# H03R00-T.net
KiCad netlist of a schematic drawn in EAGLE
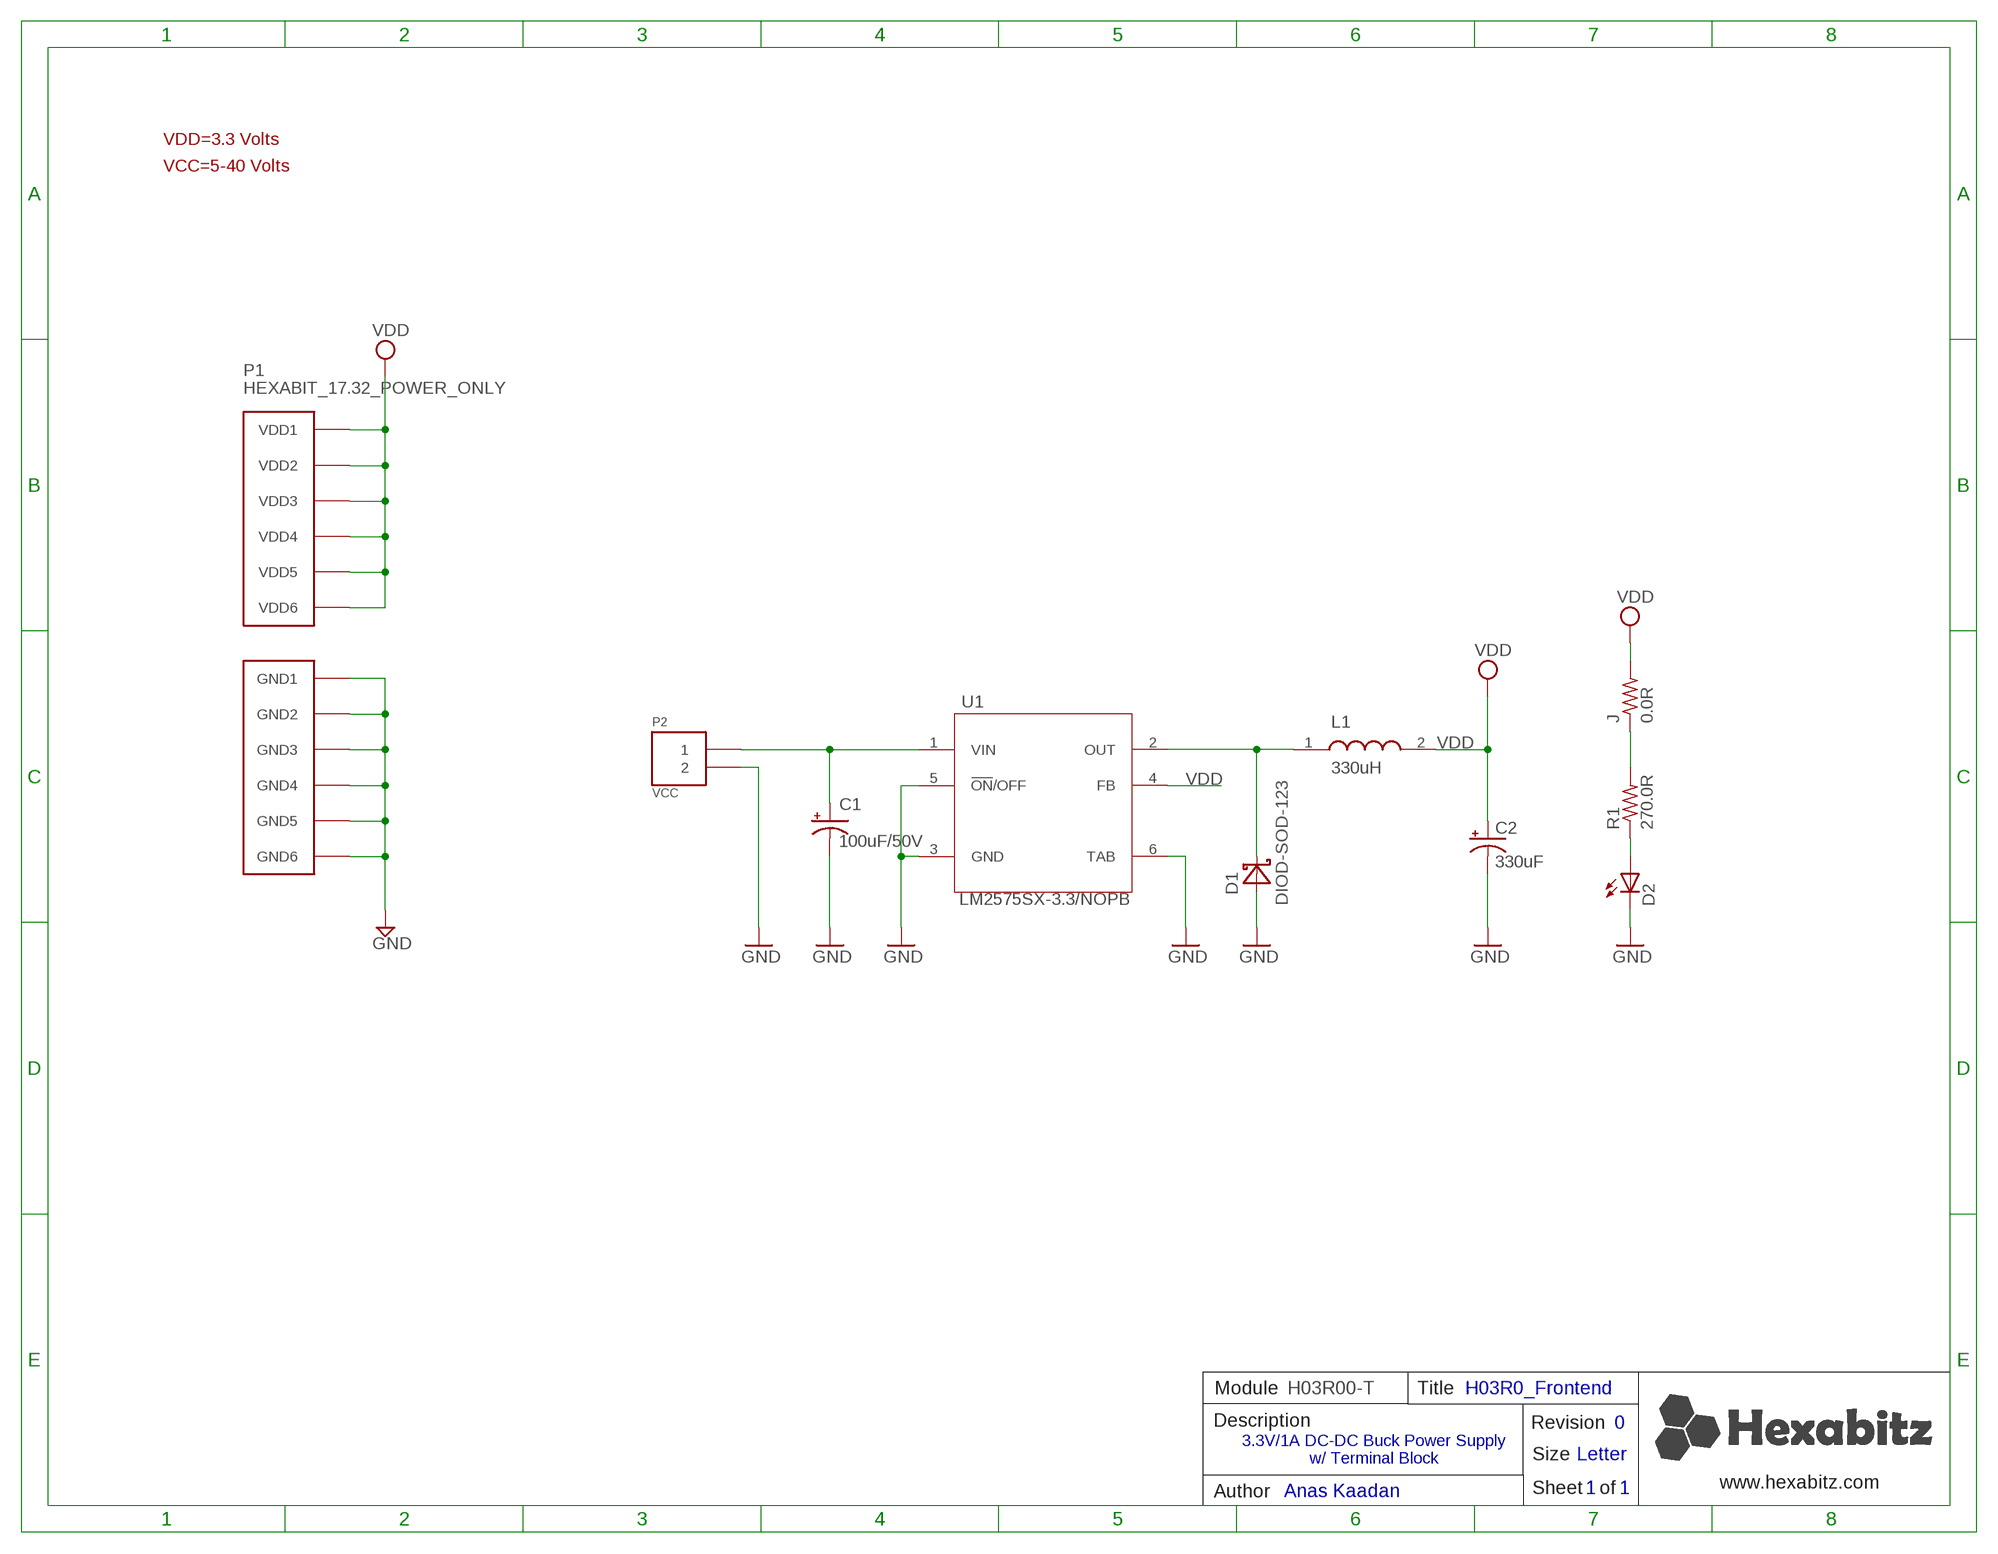
[diagram p0: schematic, sheet 1]

(export (version "E")
  (design (tool "Eeschema 10.0.6"))
  (components
    (comp (ref "C1")
      (value "100uF/50V")
      (footprint "eagle-import:E3,5-8")
      (fields
        (field (name "CAPACITANCE") "100F")
        (field (name "CPACITANCE_RATING") "±20%")
        (field (name "MFN") "Nichicon")
        (field (name "MPN") "UVR1H101MPD1TD")
        (field (name "OCTOPART_ID") "913e58b97f3b4ef9")
        (field (name "OCTOPART_URL") "http://octopart.com/uvr1h101mpd1td-nichicon-9292643")
        (field (name "VOLTAGE_RATING_DC") "50.0 V")
      )
      (libsource (lib "eagle-import") (part "CPOL-US"))
    )
    (comp (ref "C2")
      (value "330uF")
      (footprint "eagle-import:CAPPM7343X200N")
      (fields
        (field (name "MANUFACTURER_PART_NUMBER") "6TPC330MA")
        (field (name "MOUSER_PART_NUMBER") "667-6TPC330MA")
        (field (name "RS_PART_NUMBER") "1666900")
      )
      (libsource (lib "eagle-import") (part "AVX-E"))
    )
    (comp (ref "D1")
      (value "DIOD-SOD-123")
      (footprint "eagle-import:SOD123")
      (fields
        (field (name "CAPACITANCE") "1.1e-10 F")
        (field (name "CURRENT_RATING") "1.0 A")
        (field (name "MFN") "diodes")
        (field (name "MPN") "1N5819HW-7-F")
        (field (name "OCTOPART_ID") "e83e2130232537f9")
        (field (name "OCTOPART_URL") "https://octopart.com/1n5819hw-7-f-diodes+inc.-323197")
        (field (name "VOLTAGE_RATING_DC") "40.0 V")
      )
      (libsource (lib "eagle-import") (part "DIOD-SOD-123"))
    )
    (comp (ref "D2")
      (value "VLMS1300-GS08")
      (footprint "eagle-import:VLMS1300-GS08")
      (fields
        (field (name "MFN") "Vishay")
        (field (name "MPN") "VLMTG1300-GS08")
        (field (name "OCTOPART_URL") "http://octopart.com/vlmtg1300-gs08-vishay-21709202")
      )
      (libsource (lib "eagle-import") (part "VLMS1300-GS08"))
    )
    (comp (ref "J")
      (value "0.0R")
      (footprint "eagle-import:R-0603")
      (fields
        (field (name "MFN") "Yageo")
        (field (name "MPN") "RC0603JR-070RL")
        (field (name "OCTOPART_URL") "https://octopart.com/crcw06030000z0eahp-vishay-44320230")
        (field (name "RESISTANCE") "0.0 Ω")
      )
      (libsource (lib "eagle-import") (part "R-0603"))
    )
    (comp (ref "L1")
      (value "330uH")
      (footprint "eagle-import:SRR1280-150M")
      (fields
        (field (name "MANUFACTURER_PART_NUMBER") "SRR1280-331K")
        (field (name "MOUSER_PART_NUMBER") "652-SRR1280-331K")
        (field (name "RS_PART_NUMBER") "1728540")
      )
      (libsource (lib "eagle-import") (part "SRR1280-331K"))
    )
    (comp (ref "P1")
      (value "HEXABIT_17.32_POWER_ONLY")
      (footprint "eagle-import:HEXABIT_17.32_POWER_ONLY")
      (libsource (lib "eagle-import") (part "HEXABIT_?_POWER_ONLY17.32"))
    )
    (comp (ref "P2")
      (value "VCC")
      (footprint "eagle-import:1546111-2")
      (fields (field (name "MPN") "1546111-2"))
      (libsource (lib "eagle-import") (part "1546111-2"))
    )
    (comp (ref "R1")
      (value "270.0R")
      (footprint "eagle-import:R-0603")
      (fields
        (field (name "MFN") "Yageo")
        (field (name "MPN") "RC0603FR-07270RL")
        (field (name "OCTOPART_URL") "https://octopart.com/crcw0603270rjnea-vishay-39784736")
        (field (name "RESISTANCE") "270.0 Ω")
        (field (name "TOLERANCE") "±5%")
      )
      (libsource (lib "eagle-import") (part "R-0603"))
    )
    (comp (ref "U1")
      (value "LM2575SX-3.3/NOPB")
      (footprint "eagle-import:TO170P1435X457-6N")
      (fields
        (field (name "DIGI-KEY_PART_NUMBER") "LM2575SX-3.3/NOPBCT-ND")
        (field (name "MF") "Texas Instruments")
      )
      (libsource (lib "eagle-import") (part "LM2575SX-3.3/NOPB"))
    )
  )
  (nets
    (net (code "1") (name "GND") (class "Default")
      (node (ref "C1") (pin "-") (pinfunction "-_-") (pintype "passive"))
      (node (ref "C2") (pin "2") (pinfunction "-_2") (pintype "passive"))
      (node (ref "D1") (pin "1") (pinfunction "A_1") (pintype "passive"))
      (node (ref "D2") (pin "C") (pinfunction "C_C") (pintype "passive"))
      (node (ref "P1") (pin "PAD_PD10") (pinfunction "GND4_PAD_PD10") (pintype "power_in"))
      (node (ref "P1") (pin "PAD_PD11") (pinfunction "GND5_PAD_PD11") (pintype "power_in"))
      (node (ref "P1") (pin "PAD_PD12") (pinfunction "GND6_PAD_PD12") (pintype "power_in"))
      (node (ref "P1") (pin "PAD_PD7") (pinfunction "GND1_PAD_PD7") (pintype "power_in"))
      (node (ref "P1") (pin "PAD_PD8") (pinfunction "GND2_PAD_PD8") (pintype "power_in"))
      (node (ref "P1") (pin "PAD_PD9") (pinfunction "GND3_PAD_PD9") (pintype "power_in"))
      (node (ref "P2") (pin "2") (pinfunction "2_2") (pintype "power_in"))
      (node (ref "U1") (pin "3") (pinfunction "GND_3") (pintype "passive"))
      (node (ref "U1") (pin "5") (pinfunction "ON/OFF_5") (pintype "input"))
      (node (ref "U1") (pin "6") (pinfunction "TAB_6") (pintype "passive"))
    )
    (net (code "2") (name "Net-(D1-C)") (class "Default")
      (node (ref "D1") (pin "2") (pinfunction "C_2") (pintype "passive"))
      (node (ref "L1") (pin "1") (pinfunction "1_1") (pintype "bidirectional"))
      (node (ref "U1") (pin "2") (pinfunction "OUT_2") (pintype "output"))
    )
    (net (code "3") (name "Net-(D2-PadA)") (class "Default")
      (node (ref "D2") (pin "A") (pinfunction "A_A") (pintype "passive"))
      (node (ref "R1") (pin "1") (pinfunction "1_1") (pintype "passive"))
    )
    (net (code "4") (name "Net-(J-Pad1)") (class "Default")
      (node (ref "J") (pin "1") (pinfunction "1_1") (pintype "passive"))
      (node (ref "R1") (pin "2") (pinfunction "2_2") (pintype "passive"))
    )
    (net (code "5") (name "Net-(U1-VIN)") (class "Default")
      (node (ref "C1") (pin "+") (pinfunction "+_+") (pintype "passive"))
      (node (ref "P2") (pin "1") (pinfunction "1_1") (pintype "power_in"))
      (node (ref "U1") (pin "1") (pinfunction "VIN_1") (pintype "power_in"))
    )
    (net (code "6") (name "VDD") (class "Default")
      (node (ref "C2") (pin "1") (pinfunction "+_1") (pintype "passive"))
      (node (ref "J") (pin "2") (pinfunction "2_2") (pintype "passive"))
      (node (ref "L1") (pin "2") (pinfunction "2_2") (pintype "bidirectional"))
      (node (ref "P1") (pin "PAD_PU10") (pinfunction "VDD4_PAD_PU10") (pintype "power_in"))
      (node (ref "P1") (pin "PAD_PU11") (pinfunction "VDD5_PAD_PU11") (pintype "power_in"))
      (node (ref "P1") (pin "PAD_PU12") (pinfunction "VDD6_PAD_PU12") (pintype "power_in"))
      (node (ref "P1") (pin "PAD_PU7") (pinfunction "VDD1_PAD_PU7") (pintype "power_in"))
      (node (ref "P1") (pin "PAD_PU8") (pinfunction "VDD2_PAD_PU8") (pintype "power_in"))
      (node (ref "P1") (pin "PAD_PU9") (pinfunction "VDD3_PAD_PU9") (pintype "power_in"))
      (node (ref "U1") (pin "4") (pinfunction "FB_4") (pintype "input"))
    )
  )
)
